# adc.net
KiCad netlist of a schematic drawn in EAGLE
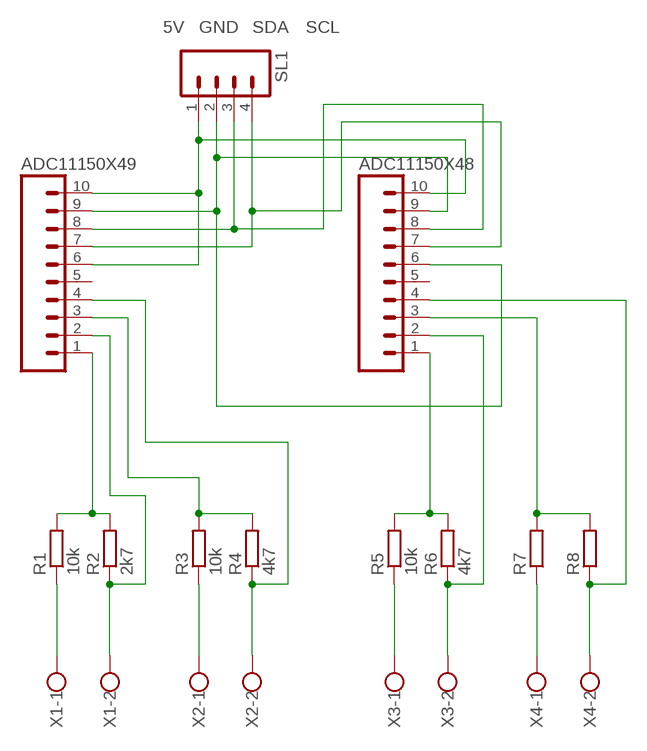
[diagram p0: schematic, sheet 1]

(export (version "E")
  (design (tool "Eeschema 10.0.6"))
  (components
    (comp (ref "ADC11150X48")
      (value "M10")
      (footprint "eagle-import:10P")
      (libsource (lib "eagle-import") (part "M10"))
    )
    (comp (ref "ADC11150X49")
      (value "M10")
      (footprint "eagle-import:10P")
      (libsource (lib "eagle-import") (part "M10"))
    )
    (comp (ref "R1")
      (value "10k")
      (footprint "eagle-import:0204_7")
      (libsource (lib "eagle-import") (part "R-EU_0204/7"))
    )
    (comp (ref "R2")
      (value "2k7")
      (footprint "eagle-import:0204_7")
      (libsource (lib "eagle-import") (part "R-EU_0204/7"))
    )
    (comp (ref "R3")
      (value "10k")
      (footprint "eagle-import:0204_7")
      (libsource (lib "eagle-import") (part "R-EU_0204/7"))
    )
    (comp (ref "R4")
      (value "4k7")
      (footprint "eagle-import:0204_7")
      (libsource (lib "eagle-import") (part "R-EU_0204/7"))
    )
    (comp (ref "R5")
      (value "10k")
      (footprint "eagle-import:0204_7")
      (libsource (lib "eagle-import") (part "R-EU_0204/7"))
    )
    (comp (ref "R6")
      (value "4k7")
      (footprint "eagle-import:0204_7")
      (libsource (lib "eagle-import") (part "R-EU_0204/7"))
    )
    (comp (ref "R7")
      (value "R-EU_0204/7")
      (footprint "eagle-import:0204_7")
      (libsource (lib "eagle-import") (part "R-EU_0204/7"))
    )
    (comp (ref "R8")
      (value "R-EU_0204/7")
      (footprint "eagle-import:0204_7")
      (libsource (lib "eagle-import") (part "R-EU_0204/7"))
    )
    (comp (ref "SL1")
      (value "M04")
      (footprint "eagle-import:04P")
      (libsource (lib "eagle-import") (part "M04"))
    )
    (comp (ref "X1")
      (value "W237-102")
      (footprint "eagle-import:W237-102")
      (fields (field (name "MPN") "237-102"))
      (libsource (lib "eagle-import") (part "W237-102"))
    )
    (comp (ref "X2")
      (value "W237-102")
      (footprint "eagle-import:W237-102")
      (fields (field (name "MPN") "237-102"))
      (libsource (lib "eagle-import") (part "W237-102"))
    )
    (comp (ref "X3")
      (value "W237-102")
      (footprint "eagle-import:W237-102")
      (fields (field (name "MPN") "237-102"))
      (libsource (lib "eagle-import") (part "W237-102"))
    )
    (comp (ref "X4")
      (value "W237-102")
      (footprint "eagle-import:W237-102")
      (fields (field (name "MPN") "237-102"))
      (libsource (lib "eagle-import") (part "W237-102"))
    )
  )
  (nets
    (net (code "1") (name "/5V") (class "Default")
      (node (ref "ADC11150X48") (pin "10") (pinfunction "10_10") (pintype "passive"))
      (node (ref "ADC11150X49") (pin "10") (pinfunction "10_10") (pintype "passive"))
      (node (ref "ADC11150X49") (pin "6") (pinfunction "6_6") (pintype "passive"))
      (node (ref "SL1") (pin "1") (pinfunction "1_1") (pintype "passive"))
    )
    (net (code "2") (name "/GND") (class "Default")
      (node (ref "ADC11150X48") (pin "6") (pinfunction "6_6") (pintype "passive"))
      (node (ref "ADC11150X48") (pin "9") (pinfunction "9_9") (pintype "passive"))
      (node (ref "ADC11150X49") (pin "9") (pinfunction "9_9") (pintype "passive"))
      (node (ref "SL1") (pin "2") (pinfunction "2_2") (pintype "passive"))
    )
    (net (code "3") (name "/SCL") (class "Default")
      (node (ref "ADC11150X48") (pin "7") (pinfunction "7_7") (pintype "passive"))
      (node (ref "ADC11150X49") (pin "7") (pinfunction "7_7") (pintype "passive"))
      (node (ref "SL1") (pin "4") (pinfunction "4_4") (pintype "passive"))
    )
    (net (code "4") (name "/SDA") (class "Default")
      (node (ref "ADC11150X48") (pin "8") (pinfunction "8_8") (pintype "passive"))
      (node (ref "ADC11150X49") (pin "8") (pinfunction "8_8") (pintype "passive"))
      (node (ref "SL1") (pin "3") (pinfunction "3_3") (pintype "passive"))
    )
    (net (code "5") (name "Net-(ADC11150X48-Pad1)") (class "Default")
      (node (ref "ADC11150X48") (pin "1") (pinfunction "1_1") (pintype "passive"))
      (node (ref "R5") (pin "2") (pinfunction "2_2") (pintype "passive"))
      (node (ref "R6") (pin "2") (pinfunction "2_2") (pintype "passive"))
    )
    (net (code "6") (name "Net-(ADC11150X48-Pad3)") (class "Default")
      (node (ref "ADC11150X48") (pin "3") (pinfunction "3_3") (pintype "passive"))
      (node (ref "R7") (pin "2") (pinfunction "2_2") (pintype "passive"))
      (node (ref "R8") (pin "2") (pinfunction "2_2") (pintype "passive"))
    )
    (net (code "7") (name "Net-(ADC11150X49-Pad1)") (class "Default")
      (node (ref "ADC11150X49") (pin "1") (pinfunction "1_1") (pintype "passive"))
      (node (ref "R1") (pin "2") (pinfunction "2_2") (pintype "passive"))
      (node (ref "R2") (pin "2") (pinfunction "2_2") (pintype "passive"))
    )
    (net (code "8") (name "Net-(ADC11150X49-Pad3)") (class "Default")
      (node (ref "ADC11150X49") (pin "3") (pinfunction "3_3") (pintype "passive"))
      (node (ref "R3") (pin "2") (pinfunction "2_2") (pintype "passive"))
      (node (ref "R4") (pin "2") (pinfunction "2_2") (pintype "passive"))
    )
    (net (code "9") (name "Net-(X1A-KL)") (class "Default")
      (node (ref "R1") (pin "1") (pinfunction "1_1") (pintype "passive"))
      (node (ref "X1") (pin "1") (pinfunction "KL_1") (pintype "passive"))
    )
    (net (code "10") (name "Net-(X1B-KL)") (class "Default")
      (node (ref "ADC11150X49") (pin "2") (pinfunction "2_2") (pintype "passive"))
      (node (ref "R2") (pin "1") (pinfunction "1_1") (pintype "passive"))
      (node (ref "X1") (pin "2") (pinfunction "KL_2") (pintype "passive"))
    )
    (net (code "11") (name "Net-(X2A-KL)") (class "Default")
      (node (ref "R3") (pin "1") (pinfunction "1_1") (pintype "passive"))
      (node (ref "X2") (pin "1") (pinfunction "KL_1") (pintype "passive"))
    )
    (net (code "12") (name "Net-(X2B-KL)") (class "Default")
      (node (ref "ADC11150X49") (pin "4") (pinfunction "4_4") (pintype "passive"))
      (node (ref "R4") (pin "1") (pinfunction "1_1") (pintype "passive"))
      (node (ref "X2") (pin "2") (pinfunction "KL_2") (pintype "passive"))
    )
    (net (code "13") (name "Net-(X3A-KL)") (class "Default")
      (node (ref "R5") (pin "1") (pinfunction "1_1") (pintype "passive"))
      (node (ref "X3") (pin "1") (pinfunction "KL_1") (pintype "passive"))
    )
    (net (code "14") (name "Net-(X3B-KL)") (class "Default")
      (node (ref "ADC11150X48") (pin "2") (pinfunction "2_2") (pintype "passive"))
      (node (ref "R6") (pin "1") (pinfunction "1_1") (pintype "passive"))
      (node (ref "X3") (pin "2") (pinfunction "KL_2") (pintype "passive"))
    )
    (net (code "15") (name "Net-(X4A-KL)") (class "Default")
      (node (ref "R7") (pin "1") (pinfunction "1_1") (pintype "passive"))
      (node (ref "X4") (pin "1") (pinfunction "KL_1") (pintype "passive"))
    )
    (net (code "16") (name "Net-(X4B-KL)") (class "Default")
      (node (ref "ADC11150X48") (pin "4") (pinfunction "4_4") (pintype "passive"))
      (node (ref "R8") (pin "1") (pinfunction "1_1") (pintype "passive"))
      (node (ref "X4") (pin "2") (pinfunction "KL_2") (pintype "passive"))
    )
    (net (code "17") (name "unconnected-(ADC11150X48-Pad5)") (class "Default")
      (node (ref "ADC11150X48") (pin "5") (pinfunction "5_5") (pintype "passive"))
    )
    (net (code "18") (name "unconnected-(ADC11150X49-Pad5)") (class "Default")
      (node (ref "ADC11150X49") (pin "5") (pinfunction "5_5") (pintype "passive"))
    )
  )
)
